# 780-00012-P4_Sch_M2_Focus_Drive_old.net
KiCad netlist of a schematic drawn in Altium Designer
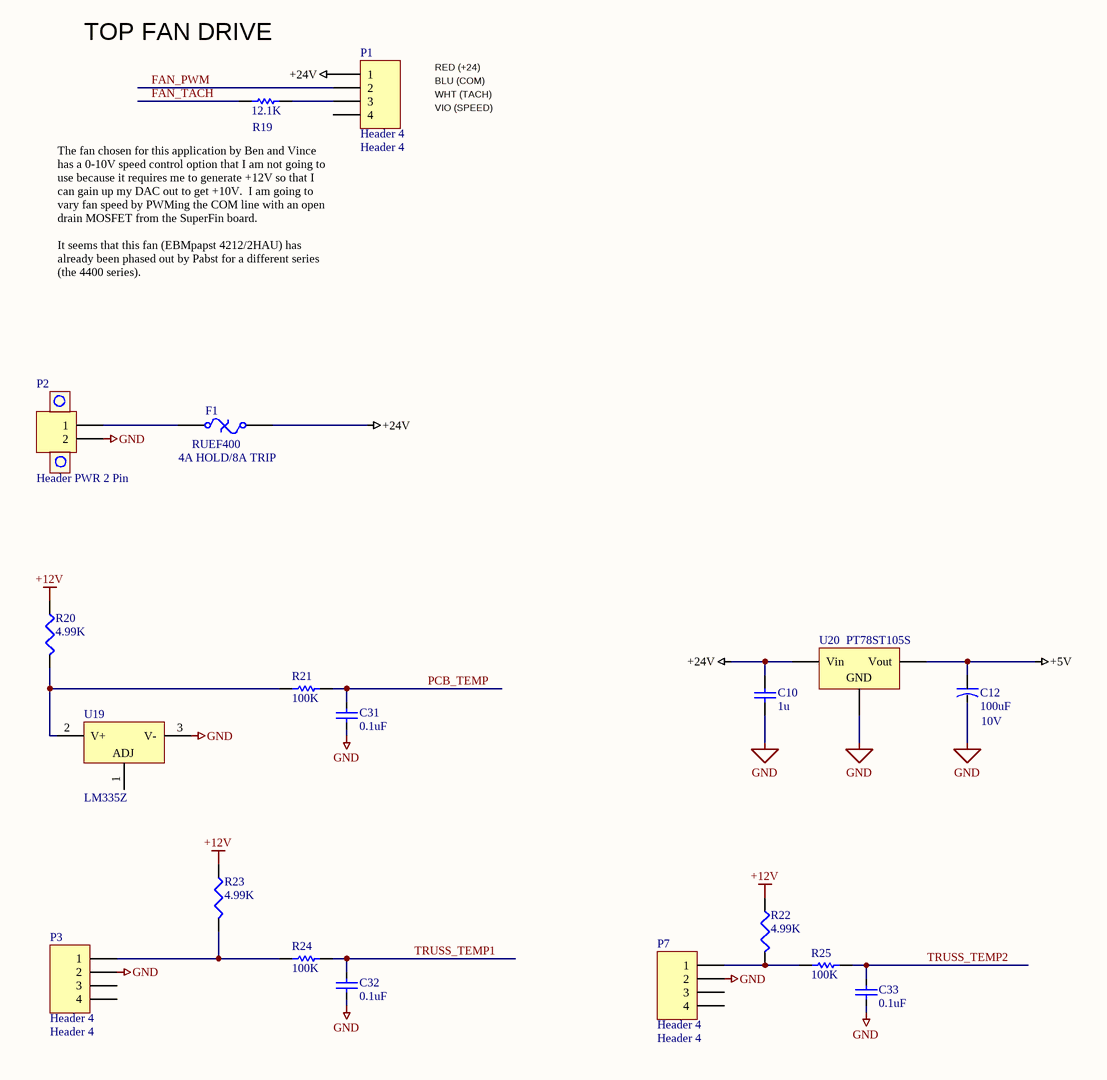
[diagram p0: 780-00012-P4, Sch M2 Focus Drive_old.SchDoc]

(export (version "E")
  (design (tool "Eeschema 10.0.6"))
  (components
    (comp (ref "C10")
      (value "1u")
      (footprint "2012[0805]")
      (description "Capacitor")
      (fields (field (name "MANUFACTURER") "Taiyo Yuden"))
      (libsource (lib "Miscellaneous Devices") (part "Cap"))
    )
    (comp (ref "C12")
      (value "10V")
      (footprint "SMD_CAP_7343")
      (description "outline 6.0mm x 3.2mm")
      (fields (field (name "MANUFACTURER") "kEMET") (field (name "ALTIUM_VALUE") "100uF"))
      (libsource (lib "Richs Schematic Components") (part "Cap Tant 35V"))
    )
    (comp (ref "C31")
      (value "0.1uF")
      (footprint "SMD_0805")
      (description "Capacitor")
      (fields (field (name "MANUFACTURER") "AVX") (field (name "Comment") "Cap SMD"))
      (libsource (lib "Richs Schematic Components") (part "Cap SMD"))
    )
    (comp (ref "C32")
      (value "0.1uF")
      (footprint "SMD_0805")
      (description "Capacitor")
      (fields (field (name "MANUFACTURER") "AVX") (field (name "Comment") "Cap SMD"))
      (libsource (lib "Richs Schematic Components") (part "Cap SMD"))
    )
    (comp (ref "C33")
      (value "0.1uF")
      (footprint "SMD_0805")
      (description "Capacitor")
      (fields (field (name "MANUFACTURER") "AVX") (field (name "Comment") "Cap SMD"))
      (libsource (lib "Richs Schematic Components") (part "Cap SMD"))
    )
    (comp (ref "F1")
      (value "RUEF400")
      (footprint "PolySwitch Radial 0.2")
      (description "PolySwitch RUE Series")
      (fields
        (field (name "MANUFACTURER") "Tyco Electronics")
        (field (name "ALTIUM_VALUE") "4A HOLD/8A TRIP")
      )
      (libsource (lib "Richs Schematic Components") (part "Fuse Thermal"))
    )
    (comp (ref "P1")
      (value "Header 4")
      (footprint "HDR1X4 for IDC")
      (description "Header, 4-Pin")
      (fields (field (name "ALTIUM_VALUE") "Header 4"))
      (libsource (lib "Richs Schematic Components") (part "Header 4"))
    )
    (comp (ref "P2")
      (value "Header PWR 2 Pin")
      (footprint "HDR-2 pin w/screw")
      (description "Header, 2-Pin")
      (libsource (lib "Richs Schematic Components") (part "Header 2 PWR"))
    )
    (comp (ref "P3")
      (value "Header 4")
      (footprint "HDR1X4 for IDC")
      (description "Header, 4-Pin")
      (fields (field (name "ALTIUM_VALUE") "Header 4"))
      (libsource (lib "") (part "Header 4_1"))
    )
    (comp (ref "P7")
      (value "Header 4")
      (footprint "HDR1X4 for IDC")
      (description "Header, 4-Pin")
      (fields (field (name "ALTIUM_VALUE") "Header 4"))
      (libsource (lib "") (part "Header 4_1"))
    )
    (comp (ref "R19")
      (value "12.1K")
      (footprint "SMD_0805")
      (description "Resistor 0805")
      (fields (field (name "MANUFACTURER") "Vishay/Dale") (field (name "Comment") "Res 0805"))
      (libsource (lib "Richs Schematic Components") (part "Res SMD"))
    )
    (comp (ref "R20")
      (value "4.99K")
      (footprint "smd_0805")
      (description "Resistor")
      (fields (field (name "MANUFACTURER") "DALE") (field (name "Comment") "Res3"))
      (libsource (lib "Miscellaneous Devices") (part "Res3"))
    )
    (comp (ref "R21")
      (value "100K")
      (footprint "SMD_0805")
      (description "Resistor")
      (fields (field (name "MANUFACTURER") "Vishay/Dale") (field (name "Comment") "Res SMD"))
      (libsource (lib "Richs Schematic Components") (part "Res SMD"))
    )
    (comp (ref "R22")
      (value "4.99K")
      (footprint "smd_0805")
      (description "Resistor")
      (fields (field (name "MANUFACTURER") "DALE") (field (name "Comment") "Res3"))
      (libsource (lib "Miscellaneous Devices") (part "Res3"))
    )
    (comp (ref "R23")
      (value "4.99K")
      (footprint "smd_0805")
      (description "Resistor")
      (fields (field (name "MANUFACTURER") "DALE") (field (name "Comment") "Res3"))
      (libsource (lib "Miscellaneous Devices") (part "Res3"))
    )
    (comp (ref "R24")
      (value "100K")
      (footprint "SMD_0805")
      (description "Resistor")
      (fields (field (name "MANUFACTURER") "Vishay/Dale") (field (name "Comment") "Res SMD"))
      (libsource (lib "Richs Schematic Components") (part "Res SMD"))
    )
    (comp (ref "R25")
      (value "100K")
      (footprint "SMD_0805")
      (description "Resistor")
      (fields (field (name "MANUFACTURER") "Vishay/Dale") (field (name "Comment") "Res SMD"))
      (libsource (lib "Richs Schematic Components") (part "Res SMD"))
    )
    (comp (ref "U19")
      (value "LM335Z")
      (footprint "Z03A")
      (description "Precision Temperature Sensor")
      (fields
        (field (name "MANUFACTURER") "National Semiconductor")
        (field (name "DIGIKEYPARTNUMBER") "LM335ZNS-ND")
        (field (name "PUBLISHER") "Altium Limited")
      )
      (libsource (lib "NSC Temperature Sensor") (part "LM335Z"))
    )
    (comp (ref "U20")
      (value "PT78ST105S")
      (footprint "PSIP_3_SMD")
      (description "Voltage Regulator")
      (fields (field (name "MANUFACTURER") "Texas Instruments"))
      (libsource (lib "Miscellaneous Devices") (part "Volt Reg"))
    )
  )
  (nets
    (net (code "1") (name "+5V") (class "Default")
      (node (ref "C12") (pin "pos") (pinfunction "1_pos") (pintype "passive"))
      (node (ref "U20") (pin "3") (pinfunction "Vout_3") (pintype "passive"))
    )
    (net (code "2") (name "+12V") (class "Default")
      (node (ref "R20") (pin "1") (pinfunction "1_1") (pintype "passive"))
      (node (ref "R22") (pin "1") (pinfunction "1_1") (pintype "passive"))
      (node (ref "R23") (pin "1") (pinfunction "1_1") (pintype "passive"))
    )
    (net (code "3") (name "+24V") (class "Default")
      (node (ref "C10") (pin "1") (pinfunction "1_1") (pintype "passive"))
      (node (ref "F1") (pin "2") (pinfunction "2_2") (pintype "passive"))
      (node (ref "P1") (pin "1") (pinfunction "1_1") (pintype "passive"))
      (node (ref "U20") (pin "1") (pinfunction "Vin_1") (pintype "passive"))
    )
    (net (code "4") (name "/FAN_PWM") (class "Default")
      (node (ref "P1") (pin "2") (pinfunction "2_2") (pintype "passive"))
    )
    (net (code "5") (name "/FAN_TACH") (class "Default")
      (node (ref "R19") (pin "1") (pinfunction "1_1") (pintype "passive"))
    )
    (net (code "6") (name "/PCB_TEMP") (class "Default")
      (node (ref "C31") (pin "2") (pinfunction "2_2") (pintype "passive"))
      (node (ref "R21") (pin "1") (pinfunction "1_1") (pintype "passive"))
    )
    (net (code "7") (name "/TRUSS_TEMP1") (class "Default")
      (node (ref "C32") (pin "2") (pinfunction "2_2") (pintype "passive"))
      (node (ref "R24") (pin "1") (pinfunction "1_1") (pintype "passive"))
    )
    (net (code "8") (name "/TRUSS_TEMP2") (class "Default")
      (node (ref "C33") (pin "2") (pinfunction "2_2") (pintype "passive"))
      (node (ref "R25") (pin "1") (pinfunction "1_1") (pintype "passive"))
    )
    (net (code "9") (name "GND") (class "Default")
      (node (ref "C10") (pin "2") (pinfunction "2_2") (pintype "passive"))
      (node (ref "C12") (pin "neg") (pinfunction "2_neg") (pintype "passive"))
      (node (ref "C31") (pin "1") (pinfunction "1_1") (pintype "passive"))
      (node (ref "C32") (pin "1") (pinfunction "1_1") (pintype "passive"))
      (node (ref "C33") (pin "1") (pinfunction "1_1") (pintype "passive"))
      (node (ref "P2") (pin "2") (pinfunction "2_2") (pintype "passive"))
      (node (ref "P3") (pin "2") (pinfunction "2_2") (pintype "passive"))
      (node (ref "P7") (pin "2") (pinfunction "2_2") (pintype "passive"))
      (node (ref "U19") (pin "3") (pinfunction "V-_3") (pintype "passive"))
      (node (ref "U20") (pin "2") (pinfunction "GND_2") (pintype "passive"))
    )
    (net (code "10") (name "Net-(F1-Pad1)") (class "Default")
      (node (ref "F1") (pin "1") (pinfunction "1_1") (pintype "passive"))
      (node (ref "P2") (pin "1") (pinfunction "1_1") (pintype "passive"))
    )
    (net (code "11") (name "Net-(P1-Pad3)") (class "Default")
      (node (ref "P1") (pin "3") (pinfunction "3_3") (pintype "passive"))
      (node (ref "R19") (pin "2") (pinfunction "2_2") (pintype "passive"))
    )
    (net (code "12") (name "Net-(P3-Pad1)") (class "Default")
      (node (ref "P3") (pin "1") (pinfunction "1_1") (pintype "passive"))
      (node (ref "R23") (pin "2") (pinfunction "2_2") (pintype "passive"))
      (node (ref "R24") (pin "2") (pinfunction "2_2") (pintype "passive"))
    )
    (net (code "13") (name "Net-(P7-Pad1)") (class "Default")
      (node (ref "P7") (pin "1") (pinfunction "1_1") (pintype "passive"))
      (node (ref "R22") (pin "2") (pinfunction "2_2") (pintype "passive"))
      (node (ref "R25") (pin "2") (pinfunction "2_2") (pintype "passive"))
    )
    (net (code "14") (name "Net-(U19-V+)") (class "Default")
      (node (ref "R20") (pin "2") (pinfunction "2_2") (pintype "passive"))
      (node (ref "R21") (pin "2") (pinfunction "2_2") (pintype "passive"))
      (node (ref "U19") (pin "2") (pinfunction "V+_2") (pintype "passive"))
    )
    (net (code "15") (name "SUPPORT") (class "Default")
      (node (ref "U20") (pin "0") (pinfunction "SUPPORT_0") (pintype "passive"))
    )
    (net (code "16") (name "unconnected-(P1-Pad4)") (class "Default")
      (node (ref "P1") (pin "4") (pinfunction "4_4") (pintype "passive"))
    )
    (net (code "17") (name "unconnected-(P3-Pad3)") (class "Default")
      (node (ref "P3") (pin "3") (pinfunction "3_3") (pintype "passive"))
    )
    (net (code "18") (name "unconnected-(P3-Pad4)") (class "Default")
      (node (ref "P3") (pin "4") (pinfunction "4_4") (pintype "passive"))
    )
    (net (code "19") (name "unconnected-(P7-Pad3)") (class "Default")
      (node (ref "P7") (pin "3") (pinfunction "3_3") (pintype "passive"))
    )
    (net (code "20") (name "unconnected-(P7-Pad4)") (class "Default")
      (node (ref "P7") (pin "4") (pinfunction "4_4") (pintype "passive"))
    )
    (net (code "21") (name "unconnected-(U19-ADJ-Pad1)") (class "Default")
      (node (ref "U19") (pin "1") (pinfunction "ADJ_1") (pintype "passive"))
    )
  )
)
